# FuelGauge.net
KiCad netlist of a schematic drawn in Altium Designer
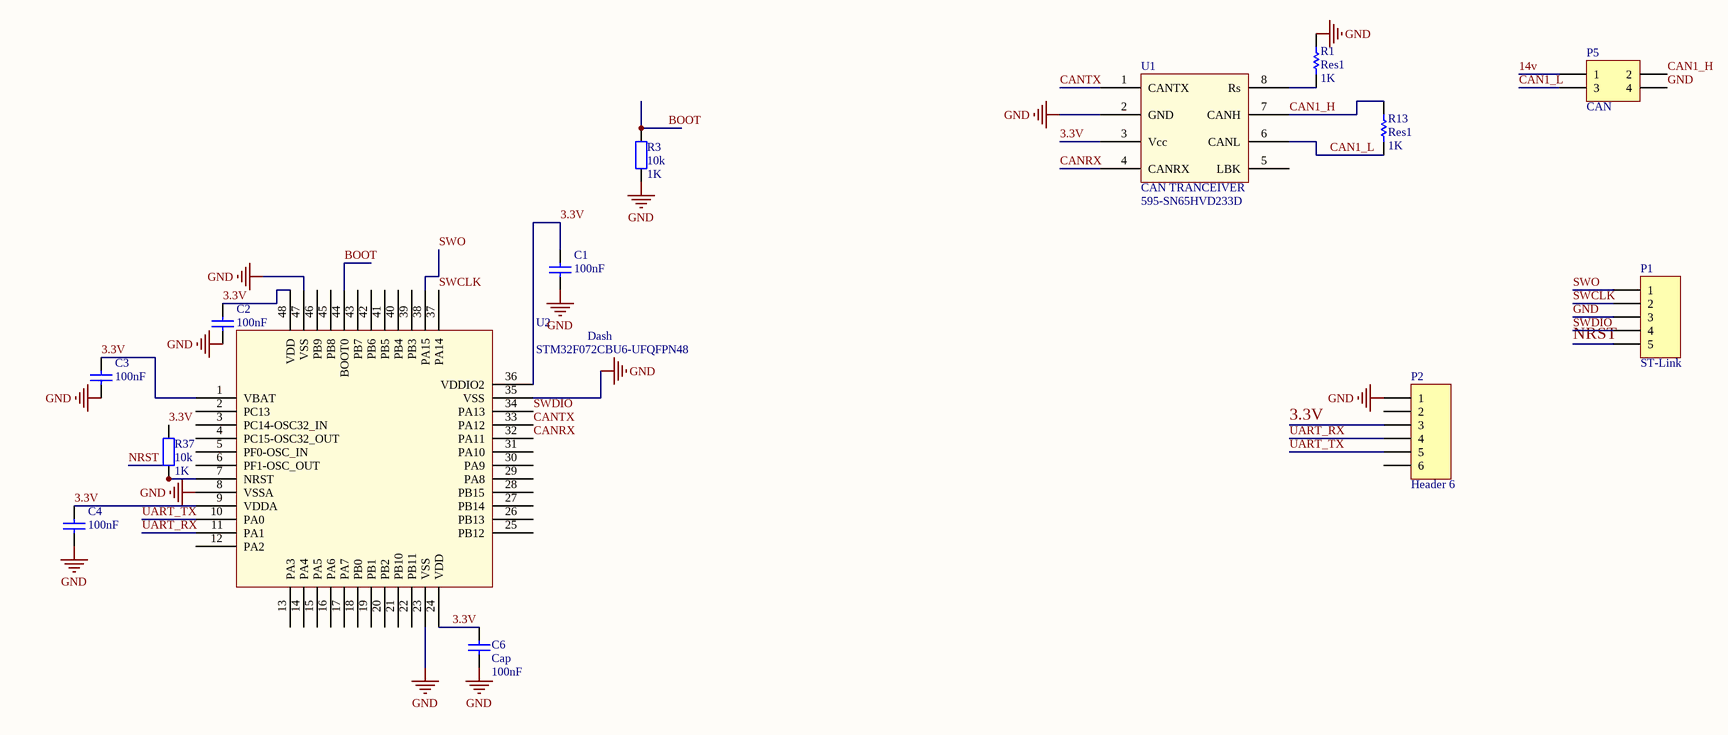
[diagram p0: FuelGauge.SchDoc]

(export (version "E")
  (design (tool "Eeschema 10.0.6"))
  (components
    (comp (ref "C1")
      (value "100nF")
      (footprint "R0805")
      (description "Capacitor (Semiconductor SIM Model)")
      (fields (field (name "PUBLISHER") "Altium Limited"))
      (libsource (lib "Miscellaneous Devices") (part "Cap Semi"))
    )
    (comp (ref "C2")
      (value "100nF")
      (footprint "R0805")
      (description "Capacitor (Semiconductor SIM Model)")
      (fields (field (name "PUBLISHER") "Altium Limited"))
      (libsource (lib "Miscellaneous Devices") (part "Cap Semi"))
    )
    (comp (ref "C3")
      (value "100nF")
      (footprint "R0805")
      (description "Capacitor (Semiconductor SIM Model)")
      (fields (field (name "PUBLISHER") "Altium Limited"))
      (libsource (lib "Miscellaneous Devices") (part "Cap Semi"))
    )
    (comp (ref "C4")
      (value "100nF")
      (footprint "R0805")
      (description "Capacitor (Semiconductor SIM Model)")
      (fields (field (name "PUBLISHER") "Altium Limited"))
      (libsource (lib "Miscellaneous Devices") (part "Cap Semi"))
    )
    (comp (ref "C6")
      (value "Cap")
      (footprint "R0805")
      (description "Capacitor")
      (fields (field (name "ALTIUM_VALUE") "100nF") (field (name "PUBLISHER") "Altium Limited"))
      (libsource (lib "Miscellaneous Devices") (part "Cap"))
    )
    (comp (ref "P1")
      (value "ST-Link")
      (footprint "SMD 5Wire - Small")
      (description "Header, 5-Pin")
      (fields (field (name "PUBLISHER") "Altium Limited"))
      (libsource (lib "Miscellaneous Connectors") (part "Header 5"))
    )
    (comp (ref "P2")
      (value "Header 6")
      (footprint "HDR1X6")
      (description "Header, 6-Pin")
      (fields (field (name "PUBLISHER") "Altium Limited"))
      (libsource (lib "Miscellaneous Connectors") (part "Header 6"))
    )
    (comp (ref "P5")
      (value "CAN")
      (footprint "SMD 4Wire")
      (description "Header, 2-Pin, Dual row, Right Angle")
      (fields (field (name "PUBLISHER") "Altium Limited"))
      (libsource (lib "Miscellaneous Connectors") (part "Header 2X2H"))
    )
    (comp (ref "R1")
      (value "Res1")
      (footprint "R0805")
      (description "Resistor")
      (fields (field (name "ALTIUM_VALUE") "1K") (field (name "PUBLISHER") "Altium Limited"))
      (libsource (lib "Miscellaneous Devices") (part "Res1"))
    )
    (comp (ref "R3")
      (value "10k")
      (footprint "R0805")
      (description "Resistor")
      (fields (field (name "ALTIUM_VALUE") "1K") (field (name "PUBLISHER") "Altium Limited"))
      (libsource (lib "Miscellaneous Devices") (part "Res2"))
    )
    (comp (ref "R13")
      (value "Res1")
      (footprint "R0805")
      (description "Resistor")
      (fields (field (name "ALTIUM_VALUE") "1K") (field (name "PUBLISHER") "Altium Limited"))
      (libsource (lib "Miscellaneous Devices") (part "Res1"))
    )
    (comp (ref "R37")
      (value "10k")
      (footprint "R0805")
      (description "Resistor")
      (fields (field (name "ALTIUM_VALUE") "1K") (field (name "PUBLISHER") "Altium Limited"))
      (libsource (lib "Miscellaneous Devices") (part "Res2"))
    )
    (comp (ref "U1")
      (value "CAN TRANCEIVER")
      (footprint "SOP8")
      (fields (field (name "SUPPLIER PART NUMBER 1") "595-SN65HVD233D"))
      (libsource (lib "Misc_ICs-1") (part "595-SN65HVD233"))
    )
    (comp (ref "U2")
      (value "Dash")
      (footprint "STM32F072CBU6 - No Heatsink")
      (description "PDM Mk21 MICRO")
      (fields
        (field (name "MANUFACTURER") "ST Microelectrics")
        (field (name "PART NUMBER") "STM32F072CBU6-UFQFPN48")
      )
      (libsource (lib "STM32_1") (part "STM32F072CBU6"))
    )
  )
  (nets
    (net (code "1") (name "/3.3V") (class "Default")
      (node (ref "C1") (pin "2") (pinfunction "2_2") (pintype "passive"))
      (node (ref "C2") (pin "2") (pinfunction "2_2") (pintype "passive"))
      (node (ref "C3") (pin "2") (pinfunction "2_2") (pintype "passive"))
      (node (ref "C4") (pin "2") (pinfunction "2_2") (pintype "passive"))
      (node (ref "C6") (pin "1") (pinfunction "1_1") (pintype "passive"))
      (node (ref "P2") (pin "3") (pinfunction "3_3") (pintype "passive"))
      (node (ref "R37") (pin "2") (pinfunction "2_2") (pintype "passive"))
      (node (ref "U1") (pin "3") (pinfunction "Vcc_3") (pintype "passive"))
      (node (ref "U2") (pin "1") (pinfunction "VBAT_1") (pintype "passive"))
      (node (ref "U2") (pin "24") (pinfunction "VDD_24") (pintype "passive"))
      (node (ref "U2") (pin "36") (pinfunction "VDDIO2_36") (pintype "passive"))
      (node (ref "U2") (pin "48") (pinfunction "VDD_48") (pintype "passive"))
      (node (ref "U2") (pin "9") (pinfunction "VDDA_9") (pintype "passive"))
    )
    (net (code "2") (name "/14v") (class "Default")
      (node (ref "P5") (pin "1") (pinfunction "1_1") (pintype "passive"))
    )
    (net (code "3") (name "/BOOT") (class "Default")
      (node (ref "R3") (pin "2") (pinfunction "2_2") (pintype "passive"))
      (node (ref "U2") (pin "44") (pinfunction "BOOT0_44") (pintype "passive"))
    )
    (net (code "4") (name "/CAN1_H") (class "Default")
      (node (ref "P5") (pin "2") (pinfunction "2_2") (pintype "passive"))
      (node (ref "R13") (pin "2") (pinfunction "2_2") (pintype "passive"))
      (node (ref "U1") (pin "7") (pinfunction "CANH_7") (pintype "passive"))
    )
    (net (code "5") (name "/CAN1_L") (class "Default")
      (node (ref "P5") (pin "3") (pinfunction "3_3") (pintype "passive"))
      (node (ref "R13") (pin "1") (pinfunction "1_1") (pintype "passive"))
      (node (ref "U1") (pin "6") (pinfunction "CANL_6") (pintype "passive"))
    )
    (net (code "6") (name "/CANRX") (class "Default")
      (node (ref "U1") (pin "4") (pinfunction "CANRX_4") (pintype "passive"))
      (node (ref "U2") (pin "32") (pinfunction "PA11_32") (pintype "passive"))
    )
    (net (code "7") (name "/CANTX") (class "Default")
      (node (ref "U1") (pin "1") (pinfunction "CANTX_1") (pintype "passive"))
      (node (ref "U2") (pin "33") (pinfunction "PA12_33") (pintype "passive"))
    )
    (net (code "8") (name "/NRST") (class "Default")
      (node (ref "P1") (pin "5") (pinfunction "5_5") (pintype "passive"))
      (node (ref "R37") (pin "1") (pinfunction "1_1") (pintype "passive"))
      (node (ref "U2") (pin "7") (pinfunction "NRST_7") (pintype "passive"))
    )
    (net (code "9") (name "/SWCLK") (class "Default")
      (node (ref "P1") (pin "2") (pinfunction "2_2") (pintype "passive"))
      (node (ref "U2") (pin "37") (pinfunction "PA14_37") (pintype "passive"))
    )
    (net (code "10") (name "/SWDIO") (class "Default")
      (node (ref "P1") (pin "4") (pinfunction "4_4") (pintype "passive"))
      (node (ref "U2") (pin "34") (pinfunction "PA13_34") (pintype "passive"))
    )
    (net (code "11") (name "/SWO") (class "Default")
      (node (ref "P1") (pin "1") (pinfunction "1_1") (pintype "passive"))
      (node (ref "U2") (pin "38") (pinfunction "PA15_38") (pintype "passive"))
    )
    (net (code "12") (name "/UART_RX") (class "Default")
      (node (ref "P2") (pin "4") (pinfunction "4_4") (pintype "passive"))
      (node (ref "U2") (pin "11") (pinfunction "PA1_11") (pintype "passive"))
    )
    (net (code "13") (name "/UART_TX") (class "Default")
      (node (ref "P2") (pin "5") (pinfunction "5_5") (pintype "passive"))
      (node (ref "U2") (pin "10") (pinfunction "PA0_10") (pintype "passive"))
    )
    (net (code "14") (name "GND") (class "Default")
      (node (ref "C1") (pin "1") (pinfunction "1_1") (pintype "passive"))
      (node (ref "C2") (pin "1") (pinfunction "1_1") (pintype "passive"))
      (node (ref "C3") (pin "1") (pinfunction "1_1") (pintype "passive"))
      (node (ref "C4") (pin "1") (pinfunction "1_1") (pintype "passive"))
      (node (ref "C6") (pin "2") (pinfunction "2_2") (pintype "passive"))
      (node (ref "P1") (pin "3") (pinfunction "3_3") (pintype "passive"))
      (node (ref "P2") (pin "1") (pinfunction "1_1") (pintype "passive"))
      (node (ref "P5") (pin "4") (pinfunction "4_4") (pintype "passive"))
      (node (ref "R1") (pin "2") (pinfunction "2_2") (pintype "passive"))
      (node (ref "R3") (pin "1") (pinfunction "1_1") (pintype "passive"))
      (node (ref "U1") (pin "2") (pinfunction "GND_2") (pintype "passive"))
      (node (ref "U2") (pin "23") (pinfunction "VSS_23") (pintype "passive"))
      (node (ref "U2") (pin "35") (pinfunction "VSS_35") (pintype "passive"))
      (node (ref "U2") (pin "47") (pinfunction "VSS_47") (pintype "passive"))
      (node (ref "U2") (pin "8") (pinfunction "VSSA_8") (pintype "passive"))
    )
    (net (code "15") (name "Net-(U1-Rs)") (class "Default")
      (node (ref "R1") (pin "1") (pinfunction "1_1") (pintype "passive"))
      (node (ref "U1") (pin "8") (pinfunction "Rs_8") (pintype "passive"))
    )
    (net (code "16") (name "unconnected-(P2-Pad2)") (class "Default")
      (node (ref "P2") (pin "2") (pinfunction "2_2") (pintype "passive"))
    )
    (net (code "17") (name "unconnected-(P2-Pad6)") (class "Default")
      (node (ref "P2") (pin "6") (pinfunction "6_6") (pintype "passive"))
    )
    (net (code "18") (name "unconnected-(U1-LBK-Pad5)") (class "Default")
      (node (ref "U1") (pin "5") (pinfunction "LBK_5") (pintype "passive"))
    )
    (net (code "19") (name "unconnected-(U2-PA2-Pad12)") (class "Default")
      (node (ref "U2") (pin "12") (pinfunction "PA2_12") (pintype "passive"))
    )
    (net (code "20") (name "unconnected-(U2-PA3-Pad13)") (class "Default")
      (node (ref "U2") (pin "13") (pinfunction "PA3_13") (pintype "passive"))
    )
    (net (code "21") (name "unconnected-(U2-PA4-Pad14)") (class "Default")
      (node (ref "U2") (pin "14") (pinfunction "PA4_14") (pintype "passive"))
    )
    (net (code "22") (name "unconnected-(U2-PA5-Pad15)") (class "Default")
      (node (ref "U2") (pin "15") (pinfunction "PA5_15") (pintype "passive"))
    )
    (net (code "23") (name "unconnected-(U2-PA6-Pad16)") (class "Default")
      (node (ref "U2") (pin "16") (pinfunction "PA6_16") (pintype "passive"))
    )
    (net (code "24") (name "unconnected-(U2-PA7-Pad17)") (class "Default")
      (node (ref "U2") (pin "17") (pinfunction "PA7_17") (pintype "passive"))
    )
    (net (code "25") (name "unconnected-(U2-PA8-Pad29)") (class "Default")
      (node (ref "U2") (pin "29") (pinfunction "PA8_29") (pintype "passive"))
    )
    (net (code "26") (name "unconnected-(U2-PA9-Pad30)") (class "Default")
      (node (ref "U2") (pin "30") (pinfunction "PA9_30") (pintype "passive"))
    )
    (net (code "27") (name "unconnected-(U2-PA10-Pad31)") (class "Default")
      (node (ref "U2") (pin "31") (pinfunction "PA10_31") (pintype "passive"))
    )
    (net (code "28") (name "unconnected-(U2-PB0-Pad18)") (class "Default")
      (node (ref "U2") (pin "18") (pinfunction "PB0_18") (pintype "passive"))
    )
    (net (code "29") (name "unconnected-(U2-PB1-Pad19)") (class "Default")
      (node (ref "U2") (pin "19") (pinfunction "PB1_19") (pintype "passive"))
    )
    (net (code "30") (name "unconnected-(U2-PB2-Pad20)") (class "Default")
      (node (ref "U2") (pin "20") (pinfunction "PB2_20") (pintype "passive"))
    )
    (net (code "31") (name "unconnected-(U2-PB3-Pad39)") (class "Default")
      (node (ref "U2") (pin "39") (pinfunction "PB3_39") (pintype "passive"))
    )
    (net (code "32") (name "unconnected-(U2-PB4-Pad40)") (class "Default")
      (node (ref "U2") (pin "40") (pinfunction "PB4_40") (pintype "passive"))
    )
    (net (code "33") (name "unconnected-(U2-PB5-Pad41)") (class "Default")
      (node (ref "U2") (pin "41") (pinfunction "PB5_41") (pintype "passive"))
    )
    (net (code "34") (name "unconnected-(U2-PB6-Pad42)") (class "Default")
      (node (ref "U2") (pin "42") (pinfunction "PB6_42") (pintype "passive"))
    )
    (net (code "35") (name "unconnected-(U2-PB7-Pad43)") (class "Default")
      (node (ref "U2") (pin "43") (pinfunction "PB7_43") (pintype "passive"))
    )
    (net (code "36") (name "unconnected-(U2-PB8-Pad45)") (class "Default")
      (node (ref "U2") (pin "45") (pinfunction "PB8_45") (pintype "passive"))
    )
    (net (code "37") (name "unconnected-(U2-PB9-Pad46)") (class "Default")
      (node (ref "U2") (pin "46") (pinfunction "PB9_46") (pintype "passive"))
    )
    (net (code "38") (name "unconnected-(U2-PB10-Pad21)") (class "Default")
      (node (ref "U2") (pin "21") (pinfunction "PB10_21") (pintype "passive"))
    )
    (net (code "39") (name "unconnected-(U2-PB11-Pad22)") (class "Default")
      (node (ref "U2") (pin "22") (pinfunction "PB11_22") (pintype "passive"))
    )
    (net (code "40") (name "unconnected-(U2-PB12-Pad25)") (class "Default")
      (node (ref "U2") (pin "25") (pinfunction "PB12_25") (pintype "passive"))
    )
    (net (code "41") (name "unconnected-(U2-PB13-Pad26)") (class "Default")
      (node (ref "U2") (pin "26") (pinfunction "PB13_26") (pintype "passive"))
    )
    (net (code "42") (name "unconnected-(U2-PB14-Pad27)") (class "Default")
      (node (ref "U2") (pin "27") (pinfunction "PB14_27") (pintype "passive"))
    )
    (net (code "43") (name "unconnected-(U2-PB15-Pad28)") (class "Default")
      (node (ref "U2") (pin "28") (pinfunction "PB15_28") (pintype "passive"))
    )
    (net (code "44") (name "unconnected-(U2-PC13-Pad2)") (class "Default")
      (node (ref "U2") (pin "2") (pinfunction "PC13_2") (pintype "passive"))
    )
    (net (code "45") (name "unconnected-(U2-PC14-OSC32_IN-Pad3)") (class "Default")
      (node (ref "U2") (pin "3") (pinfunction "PC14-OSC32_IN_3") (pintype "passive"))
    )
    (net (code "46") (name "unconnected-(U2-PC15-OSC32_OUT-Pad4)") (class "Default")
      (node (ref "U2") (pin "4") (pinfunction "PC15-OSC32_OUT_4") (pintype "passive"))
    )
    (net (code "47") (name "unconnected-(U2-PF0-OSC_IN-Pad5)") (class "Default")
      (node (ref "U2") (pin "5") (pinfunction "PF0-OSC_IN_5") (pintype "passive"))
    )
    (net (code "48") (name "unconnected-(U2-PF1-OSC_OUT-Pad6)") (class "Default")
      (node (ref "U2") (pin "6") (pinfunction "PF1-OSC_OUT_6") (pintype "passive"))
    )
  )
)
